# 03_POWER.net
KiCad netlist of a schematic drawn in Altium Designer
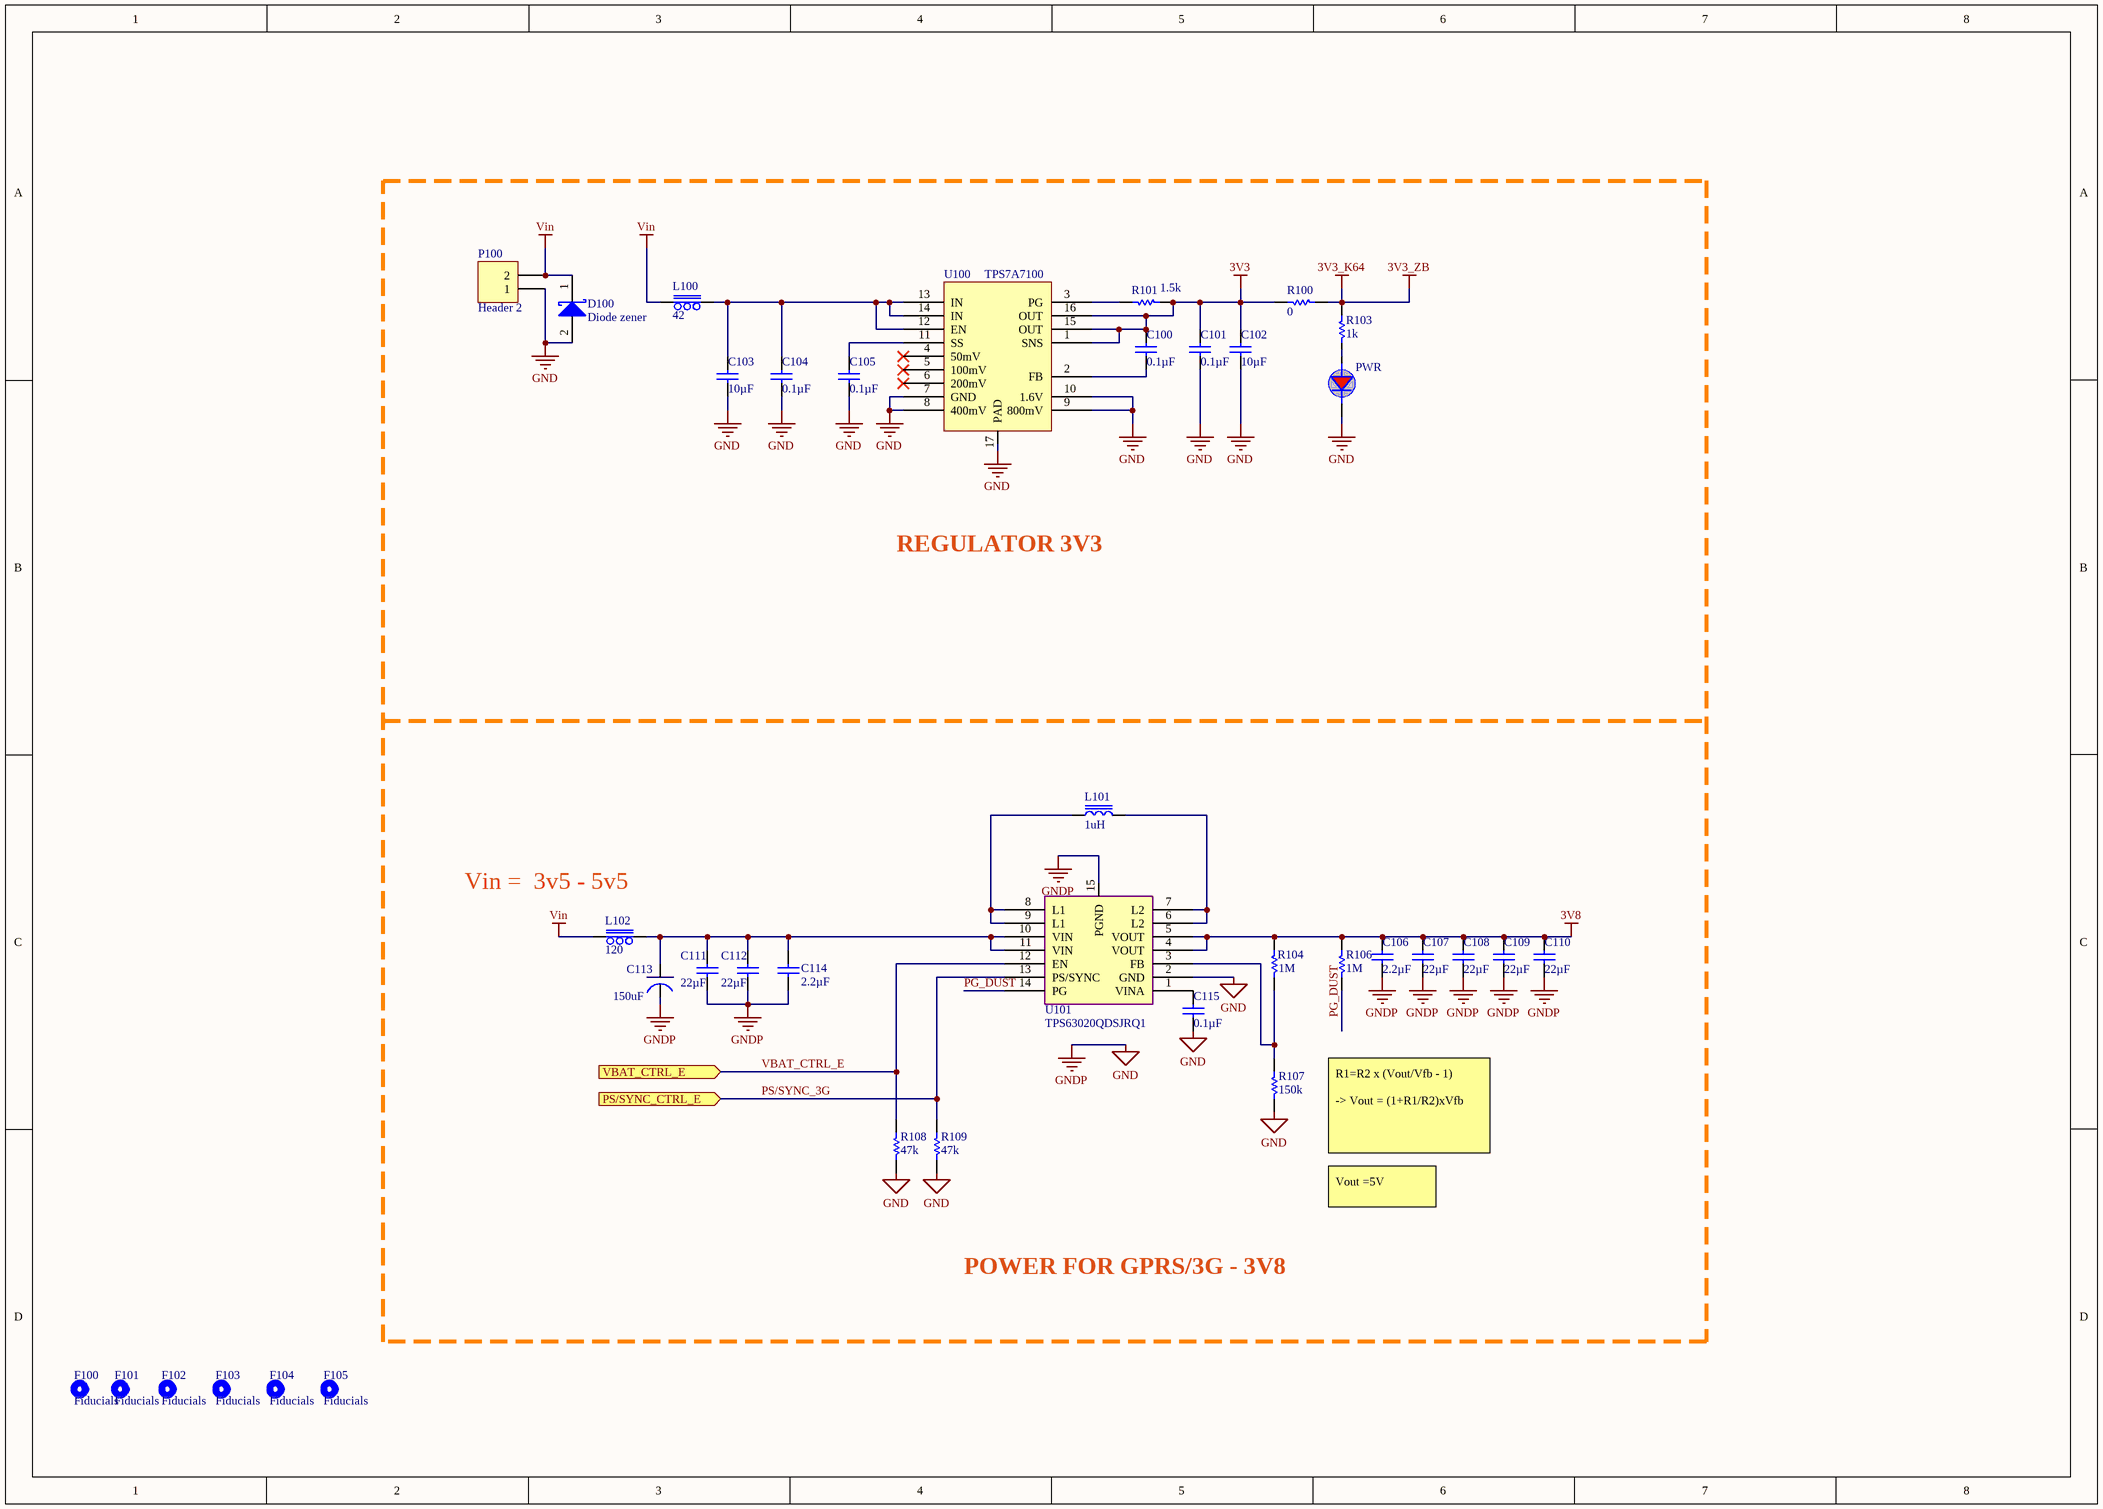
[diagram p0: [03] POWER.SchDoc]

(export (version "E")
  (design (tool "Eeschema 10.0.6"))
  (components
    (comp (ref "C100")
      (value "0.1µF")
      (footprint "0402C")
      (description "CAP CER 0.1UF 10V X7R 0402")
      (fields
        (field (name "MANUFACTURER") "Taiyo Yuden")
        (field (name "MANUFACTURER PART NUMBER") "LMK105B7104KVHF")
      )
      (libsource (lib "BinhLib") (part "CAP0.1u0402"))
    )
    (comp (ref "C101")
      (value "0.1µF")
      (footprint "0402C")
      (description "CAP CER 0.1UF 10V X7R 0402")
      (fields
        (field (name "MANUFACTURER") "Taiyo Yuden")
        (field (name "MANUFACTURER PART NUMBER") "LMK105B7104KVHF")
      )
      (libsource (lib "BinhLib") (part "CAP0.1u0402"))
    )
    (comp (ref "C102")
      (value "10µF")
      (footprint "0805 cap")
      (description "CAP CER 10UF 16V X7R 0805")
      (fields
        (field (name "MANUFACTURER") "Taiyo Yuden")
        (field (name "MANUFACTURER PART NUMBER") "EMK212BB7106MG-T")
      )
      (libsource (lib "BinhLib") (part "cap10u0805"))
    )
    (comp (ref "C103")
      (value "10µF")
      (footprint "0805 cap")
      (description "CAP CER 10UF 16V X7R 0805")
      (fields
        (field (name "MANUFACTURER") "Taiyo Yuden")
        (field (name "MANUFACTURER PART NUMBER") "EMK212BB7106MG-T")
      )
      (libsource (lib "BinhLib") (part "cap10u0805"))
    )
    (comp (ref "C104")
      (value "0.1µF")
      (footprint "0402C")
      (description "CAP CER 0.1UF 10V X7R 0402")
      (fields
        (field (name "MANUFACTURER") "Taiyo Yuden")
        (field (name "MANUFACTURER PART NUMBER") "LMK105B7104KVHF")
      )
      (libsource (lib "BinhLib") (part "CAP0.1u0402"))
    )
    (comp (ref "C105")
      (value "0.1µF")
      (footprint "0402C")
      (description "CAP CER 0.1UF 10V X7R 0402")
      (fields
        (field (name "MANUFACTURER") "Taiyo Yuden")
        (field (name "MANUFACTURER PART NUMBER") "LMK105B7104KVHF")
      )
      (libsource (lib "BinhLib") (part "CAP0.1u0402"))
    )
    (comp (ref "C106")
      (value "2.2µF")
      (footprint "0402C")
      (description "CAP CER 2.2UF 16V X5R 0402")
      (fields
        (field (name "MANUFACTURER") "Taiyo Yuden")
        (field (name "MANUFACTURER PART NUMBER") "EMK105ABJ225MV-F")
      )
      (libsource (lib "BinhLib") (part "cap2.2u0402"))
    )
    (comp (ref "C107")
      (value "22µF")
      (footprint "0805 cap")
      (description "CAP CER 22UF 16V X5R 0805")
      (fields
        (field (name "MANUFACTURER") "Taiyo Yuden")
        (field (name "MANUFACTURER PART NUMBER") "EMK212BBJ226MG-T")
      )
      (libsource (lib "BinhLib") (part "cap22u0805"))
    )
    (comp (ref "C108")
      (value "22µF")
      (footprint "0805 cap")
      (description "CAP CER 22UF 16V X5R 0805")
      (fields
        (field (name "MANUFACTURER") "Taiyo Yuden")
        (field (name "MANUFACTURER PART NUMBER") "EMK212BBJ226MG-T")
      )
      (libsource (lib "BinhLib") (part "cap22u0805"))
    )
    (comp (ref "C109")
      (value "22µF")
      (footprint "0805 cap")
      (description "CAP CER 22UF 16V X5R 0805")
      (fields
        (field (name "MANUFACTURER") "Taiyo Yuden")
        (field (name "MANUFACTURER PART NUMBER") "EMK212BBJ226MG-T")
      )
      (libsource (lib "BinhLib") (part "cap22u0805"))
    )
    (comp (ref "C110")
      (value "22µF")
      (footprint "0805 cap")
      (description "CAP CER 22UF 16V X5R 0805")
      (fields
        (field (name "MANUFACTURER") "Taiyo Yuden")
        (field (name "MANUFACTURER PART NUMBER") "EMK212BBJ226MG-T")
      )
      (libsource (lib "BinhLib") (part "cap22u0805"))
    )
    (comp (ref "C111")
      (value "22µF")
      (footprint "0805 cap")
      (description "CAP CER 22UF 16V X5R 0805")
      (fields
        (field (name "MANUFACTURER") "Taiyo Yuden")
        (field (name "MANUFACTURER PART NUMBER") "EMK212BBJ226MG-T")
      )
      (libsource (lib "BinhLib") (part "cap22u0805"))
    )
    (comp (ref "C112")
      (value "22µF")
      (footprint "0805 cap")
      (description "CAP CER 22UF 16V X5R 0805")
      (fields
        (field (name "MANUFACTURER") "Taiyo Yuden")
        (field (name "MANUFACTURER PART NUMBER") "EMK212BBJ226MG-T")
      )
      (libsource (lib "BinhLib") (part "cap22u0805"))
    )
    (comp (ref "C113")
      (value "150uF")
      (footprint "CAPD7343")
      (description "CAP TANT 150UF 10V 10% 2917")
      (fields
        (field (name "MANUFACTURER") "AVX Corporation")
        (field (name "MANUFACTURER PART NUMBER") "TPSD157K010R0085")
      )
      (libsource (lib "BinhLib") (part "CAPTan150u7343"))
    )
    (comp (ref "C114")
      (value "2.2µF")
      (footprint "0402C")
      (description "CAP CER 2.2UF 16V X5R 0402")
      (fields
        (field (name "MANUFACTURER") "Taiyo Yuden")
        (field (name "MANUFACTURER PART NUMBER") "EMK105ABJ225MV-F")
      )
      (libsource (lib "BinhLib") (part "cap2.2u0402"))
    )
    (comp (ref "C115")
      (value "0.1µF")
      (footprint "0402C")
      (description "CAP CER 0.1UF 10V X7R 0402")
      (fields
        (field (name "MANUFACTURER") "Taiyo Yuden")
        (field (name "MANUFACTURER PART NUMBER") "LMK105B7104KVHF")
      )
      (libsource (lib "BinhLib") (part "CAP0.1u0402"))
    )
    (comp (ref "D100")
      (value "Diode zener")
      (footprint "SMA-diode")
      (libsource (lib "BinhLib") (part "Diode zener"))
    )
    (comp (ref "F100")
      (value "Fiducials")
      (footprint "fiducials")
      (libsource (lib "BinhLib") (part "Fiducials"))
    )
    (comp (ref "F101")
      (value "Fiducials")
      (footprint "fiducials")
      (libsource (lib "BinhLib") (part "Fiducials"))
    )
    (comp (ref "F102")
      (value "Fiducials")
      (footprint "fiducials")
      (libsource (lib "BinhLib") (part "Fiducials"))
    )
    (comp (ref "F103")
      (value "Fiducials")
      (footprint "fiducials")
      (libsource (lib "BinhLib") (part "Fiducials"))
    )
    (comp (ref "F104")
      (value "Fiducials")
      (footprint "fiducials")
      (libsource (lib "BinhLib") (part "Fiducials"))
    )
    (comp (ref "F105")
      (value "Fiducials")
      (footprint "fiducials")
      (libsource (lib "BinhLib") (part "Fiducials"))
    )
    (comp (ref "L100")
      (value "42")
      (footprint "0805F")
      (description "FERRITE BEAD 42 OHM 0805 1LN")
      (fields
        (field (name "MANUFACTURER") "Taiyo Yuden")
        (field (name "MANUFACTURER PART NUMBER") "FBMJ2125HS420-TV")
      )
      (libsource (lib "BinhLib") (part "Ferrite Bead"))
    )
    (comp (ref "L101")
      (value "1uH")
      (footprint "INDC4040X20N")
      (description "Fixed Inductors XFL4020 Low DCR Ind 1 uH 20% 11 A Compos")
      (fields
        (field (name "MANUFACTURER") "Coilcraft")
        (field (name "MANUFACTURER PART NUMBER") "XFL4020-102MEB")
      )
      (libsource (lib "BinhLib") (part "Inductor"))
    )
    (comp (ref "L102")
      (value "120")
      (footprint "0805F")
      (fields
        (field (name "MANUFACTURER") "MURATA")
        (field (name "MANUFACTURER PART NUMBER") "BLM18PG121SN1D")
      )
      (libsource (lib "BinhLib") (part "Ferrite Bead"))
    )
    (comp (ref "P100")
      (value "Header 2")
      (footprint "HED2")
      (description "Header, 2-Pin")
      (fields (field (name "PUBLISHER") "Altium Limited"))
      (libsource (lib "BinhLib") (part "Header 2"))
    )
    (comp (ref "PWR")
      (value "~")
      (footprint "0603LED-RED")
      (description "LED RED CLEAR 0603 SMD")
      (fields
        (field (name "MANUFACTURER") "Everlight Electronics Co Ltd")
        (field (name "MANUFACTURER PART NUMBER") "QTLP600C7TR")
      )
      (libsource (lib "BinhLib") (part "LedRed0603"))
    )
    (comp (ref "R100")
      (value "0")
      (footprint "0805 Resistor")
      (description "RES SMD 0.0 OHM JUMPER 1/8W 0805")
      (fields
        (field (name "MANUFACTURER") "Panasonic Electronic Components")
        (field (name "MANUFACTURER PART NUMBER") "ERJ-6GEY0R00V")
      )
      (libsource (lib "BinhLib") (part "RES00805"))
    )
    (comp (ref "R101")
      (value "1.5k")
      (footprint "0603R")
      (description "RES SMD 1.5K OHM 1% 1/10W 0603")
      (fields
        (field (name "MANUFACTURER") "Panasonic Electronic Components")
        (field (name "MANUFACTURER PART NUMBER") "ERJ-3EKF1501V")
      )
      (libsource (lib "BinhLib") (part "RES1k50603"))
    )
    (comp (ref "R103")
      (value "1k")
      (footprint "0603R")
      (description "RES SMD 1K OHM 1% 1/10W 0603")
      (fields
        (field (name "MANUFACTURER") "Panasonic Electronic Components")
        (field (name "MANUFACTURER PART NUMBER") "ERJ-3EKF1001V")
      )
      (libsource (lib "BinhLib") (part "RES1k0603"))
    )
    (comp (ref "R104")
      (value "1M")
      (footprint "0402R")
      (description "RES SMD 1M OHM 1% 1/10W 0402")
      (fields
        (field (name "MANUFACTURER") "Panasonic Electronic Components")
        (field (name "MANUFACTURER PART NUMBER") "ERJ-2RKF1004X")
      )
      (libsource (lib "BinhLib") (part "RES1M0402"))
    )
    (comp (ref "R106")
      (value "1M")
      (footprint "0603R")
      (description "RES SMD 1M OHM 1% 1/10W 0603")
      (fields
        (field (name "MANUFACTURER") "Panasonic Electronic Components")
        (field (name "MANUFACTURER PART NUMBER") "ERJ-3EKF1004V")
      )
      (libsource (lib "BinhLib") (part "RES1M0603"))
    )
    (comp (ref "R107")
      (value "150k")
      (footprint "0402R")
      (description "RES SMD 150K OHM 1% 1/10W 0402")
      (fields
        (field (name "MANUFACTURER") "Panasonic Electronic Components")
        (field (name "MANUFACTURER PART NUMBER") "ERJ-2RKF1503X")
      )
      (libsource (lib "BinhLib") (part "Resistor"))
    )
    (comp (ref "R108")
      (value "47k")
      (footprint "0603R")
      (description "RES SMD 47K OHM 1% 1/10W 0603")
      (fields
        (field (name "MANUFACTURER") "Panasonic Electronic Components")
        (field (name "MANUFACTURER PART NUMBER") "ERJ-3EKF4702V")
      )
      (libsource (lib "BinhLib") (part "RES47k0603"))
    )
    (comp (ref "R109")
      (value "47k")
      (footprint "0603R")
      (description "RES SMD 47K OHM 1% 1/10W 0603")
      (fields
        (field (name "MANUFACTURER") "Panasonic Electronic Components")
        (field (name "MANUFACTURER PART NUMBER") "ERJ-3EKF4702V")
      )
      (libsource (lib "BinhLib") (part "RES47k0603"))
    )
    (comp (ref "U100")
      (value "TPS7A7100")
      (footprint "QFN16")
      (description "IC REG LDO FIX/ADJ 1A 16QFN")
      (fields
        (field (name "MANUFACTURER") "Texas Instruments")
        (field (name "MANUFACTURER PART NUMBER") "TPS7A7100RGTR")
      )
      (libsource (lib "BinhLib") (part "TPS7A7100"))
    )
    (comp (ref "U101")
      (value "TPS63020QDSJRQ1")
      (footprint "VSON14")
      (description "IC REG BUCK BST ADJ 3.5A")
      (fields (field (name "MANUFACTURER") "Texas Instruments"))
      (libsource (lib "BinhLib") (part "TPS63020"))
    )
  )
  (nets
    (net (code "1") (name "/PG_DUST") (class "Default")
      (node (ref "R106") (pin "1") (pinfunction "1_1") (pintype "passive"))
      (node (ref "U101") (pin "14") (pinfunction "PG_14") (pintype "passive"))
    )
    (net (code "2") (name "/PS{slash}SYNC_3G") (class "Default")
      (node (ref "R109") (pin "2") (pinfunction "2_2") (pintype "passive"))
      (node (ref "U101") (pin "13") (pinfunction "PS/SYNC_13") (pintype "passive"))
    )
    (net (code "3") (name "/VBAT_CTRL_E") (class "Default")
      (node (ref "R108") (pin "2") (pinfunction "2_2") (pintype "passive"))
      (node (ref "U101") (pin "12") (pinfunction "EN_12") (pintype "passive"))
    )
    (net (code "4") (name "3V3") (class "Default")
      (node (ref "C100") (pin "2") (pintype "passive"))
      (node (ref "C101") (pin "2") (pintype "passive"))
      (node (ref "C102") (pin "2") (pintype "passive"))
      (node (ref "R100") (pin "1") (pinfunction "1_1") (pintype "passive"))
      (node (ref "R101") (pin "2") (pinfunction "2_2") (pintype "passive"))
      (node (ref "U100") (pin "1") (pinfunction "SNS_1") (pintype "passive"))
      (node (ref "U100") (pin "15") (pinfunction "OUT_15") (pintype "passive"))
      (node (ref "U100") (pin "16") (pinfunction "OUT_16") (pintype "passive"))
    )
    (net (code "5") (name "3V3_K64") (class "Default")
      (node (ref "R100") (pin "2") (pinfunction "2_2") (pintype "passive"))
      (node (ref "R103") (pin "2") (pinfunction "2_2") (pintype "passive"))
    )
    (net (code "6") (name "3V8") (class "Default")
      (node (ref "C106") (pin "2") (pintype "passive"))
      (node (ref "C107") (pin "2") (pintype "passive"))
      (node (ref "C108") (pin "2") (pintype "passive"))
      (node (ref "C109") (pin "2") (pintype "passive"))
      (node (ref "C110") (pin "2") (pintype "passive"))
      (node (ref "R104") (pin "2") (pinfunction "2_2") (pintype "passive"))
      (node (ref "R106") (pin "2") (pinfunction "2_2") (pintype "passive"))
      (node (ref "U101") (pin "4") (pinfunction "VOUT_4") (pintype "passive"))
      (node (ref "U101") (pin "5") (pinfunction "VOUT_5") (pintype "passive"))
    )
    (net (code "7") (name "GND") (class "Default")
      (node (ref "C101") (pin "1") (pintype "passive"))
      (node (ref "C102") (pin "1") (pintype "passive"))
      (node (ref "C103") (pin "1") (pintype "passive"))
      (node (ref "C104") (pin "1") (pintype "passive"))
      (node (ref "C105") (pin "1") (pintype "passive"))
      (node (ref "C106") (pin "1") (pintype "passive"))
      (node (ref "C107") (pin "1") (pintype "passive"))
      (node (ref "C108") (pin "1") (pintype "passive"))
      (node (ref "C109") (pin "1") (pintype "passive"))
      (node (ref "C110") (pin "1") (pintype "passive"))
      (node (ref "C111") (pin "1") (pintype "passive"))
      (node (ref "C112") (pin "1") (pintype "passive"))
      (node (ref "C113") (pin "2") (pinfunction "2_2") (pintype "passive"))
      (node (ref "C114") (pin "1") (pintype "passive"))
      (node (ref "C115") (pin "1") (pintype "passive"))
      (node (ref "D100") (pin "2") (pinfunction "A_2") (pintype "passive"))
      (node (ref "P100") (pin "1") (pinfunction "1_1") (pintype "passive"))
      (node (ref "PWR") (pin "2") (pinfunction "Katot_2") (pintype "passive"))
      (node (ref "R107") (pin "1") (pinfunction "1_1") (pintype "passive"))
      (node (ref "R108") (pin "1") (pinfunction "1_1") (pintype "passive"))
      (node (ref "R109") (pin "1") (pinfunction "1_1") (pintype "passive"))
      (node (ref "U100") (pin "10") (pinfunction "1.6V_10") (pintype "passive"))
      (node (ref "U100") (pin "17") (pinfunction "PAD_17") (pintype "passive"))
      (node (ref "U100") (pin "7") (pinfunction "GND_7") (pintype "power_in"))
      (node (ref "U100") (pin "8") (pinfunction "400mV_8") (pintype "passive"))
      (node (ref "U100") (pin "9") (pinfunction "800mV_9") (pintype "passive"))
      (node (ref "U101") (pin "15") (pinfunction "PGND_15") (pintype "passive"))
      (node (ref "U101") (pin "2") (pinfunction "GND_2") (pintype "passive"))
    )
    (net (code "8") (name "Net-(C111-Pad2)") (class "Default")
      (node (ref "C111") (pin "2") (pintype "passive"))
      (node (ref "C112") (pin "2") (pintype "passive"))
      (node (ref "C113") (pin "1") (pinfunction "1_1") (pintype "passive"))
      (node (ref "C114") (pin "2") (pintype "passive"))
      (node (ref "L102") (pin "2") (pintype "passive"))
      (node (ref "U101") (pin "10") (pinfunction "VIN_10") (pintype "passive"))
      (node (ref "U101") (pin "11") (pinfunction "VIN_11") (pintype "passive"))
    )
    (net (code "9") (name "Net-(L101-Pad1)") (class "Default")
      (node (ref "L101") (pin "1") (pinfunction "1_1") (pintype "passive"))
      (node (ref "U101") (pin "8") (pinfunction "L1_8") (pintype "passive"))
      (node (ref "U101") (pin "9") (pinfunction "L1_9") (pintype "passive"))
    )
    (net (code "10") (name "Net-(L101-Pad2)") (class "Default")
      (node (ref "L101") (pin "2") (pinfunction "2_2") (pintype "passive"))
      (node (ref "U101") (pin "6") (pinfunction "L2_6") (pintype "passive"))
      (node (ref "U101") (pin "7") (pinfunction "L2_7") (pintype "passive"))
    )
    (net (code "11") (name "Net-(PWR-anot)") (class "Default")
      (node (ref "PWR") (pin "1") (pinfunction "anot_1") (pintype "passive"))
      (node (ref "R103") (pin "1") (pinfunction "1_1") (pintype "passive"))
    )
    (net (code "12") (name "Net-(U100-EN)") (class "Default")
      (node (ref "C103") (pin "2") (pintype "passive"))
      (node (ref "C104") (pin "2") (pintype "passive"))
      (node (ref "L100") (pin "2") (pintype "passive"))
      (node (ref "U100") (pin "12") (pinfunction "EN_12") (pintype "passive"))
      (node (ref "U100") (pin "13") (pinfunction "IN_13") (pintype "passive"))
      (node (ref "U100") (pin "14") (pinfunction "IN_14") (pintype "passive"))
    )
    (net (code "13") (name "Net-(U100-FB)") (class "Default")
      (node (ref "C100") (pin "1") (pintype "passive"))
      (node (ref "U100") (pin "2") (pinfunction "FB_2") (pintype "passive"))
    )
    (net (code "14") (name "Net-(U100-PG)") (class "Default")
      (node (ref "R101") (pin "1") (pinfunction "1_1") (pintype "passive"))
      (node (ref "U100") (pin "3") (pinfunction "PG_3") (pintype "passive"))
    )
    (net (code "15") (name "Net-(U100-SS)") (class "Default")
      (node (ref "C105") (pin "2") (pintype "passive"))
      (node (ref "U100") (pin "11") (pinfunction "SS_11") (pintype "passive"))
    )
    (net (code "16") (name "Net-(U101-FB)") (class "Default")
      (node (ref "R104") (pin "1") (pinfunction "1_1") (pintype "passive"))
      (node (ref "R107") (pin "2") (pinfunction "2_2") (pintype "passive"))
      (node (ref "U101") (pin "3") (pinfunction "FB_3") (pintype "passive"))
    )
    (net (code "17") (name "Net-(U101-VINA)") (class "Default")
      (node (ref "C115") (pin "2") (pintype "passive"))
      (node (ref "U101") (pin "1") (pinfunction "VINA_1") (pintype "passive"))
    )
    (net (code "18") (name "Vin") (class "Default")
      (node (ref "D100") (pin "1") (pinfunction "K_1") (pintype "passive"))
      (node (ref "L100") (pin "1") (pintype "passive"))
      (node (ref "L102") (pin "1") (pintype "passive"))
      (node (ref "P100") (pin "2") (pinfunction "2_2") (pintype "passive"))
    )
    (net (code "19") (name "unconnected-(U100-50mV-Pad4)") (class "Default")
      (node (ref "U100") (pin "4") (pinfunction "50mV_4") (pintype "passive+no_connect"))
    )
    (net (code "20") (name "unconnected-(U100-100mV-Pad5)") (class "Default")
      (node (ref "U100") (pin "5") (pinfunction "100mV_5") (pintype "passive+no_connect"))
    )
    (net (code "21") (name "unconnected-(U100-200mV-Pad6)") (class "Default")
      (node (ref "U100") (pin "6") (pinfunction "200mV_6") (pintype "passive+no_connect"))
    )
  )
)
